# Sheet2.net
KiCad netlist of a schematic drawn in Altium Designer
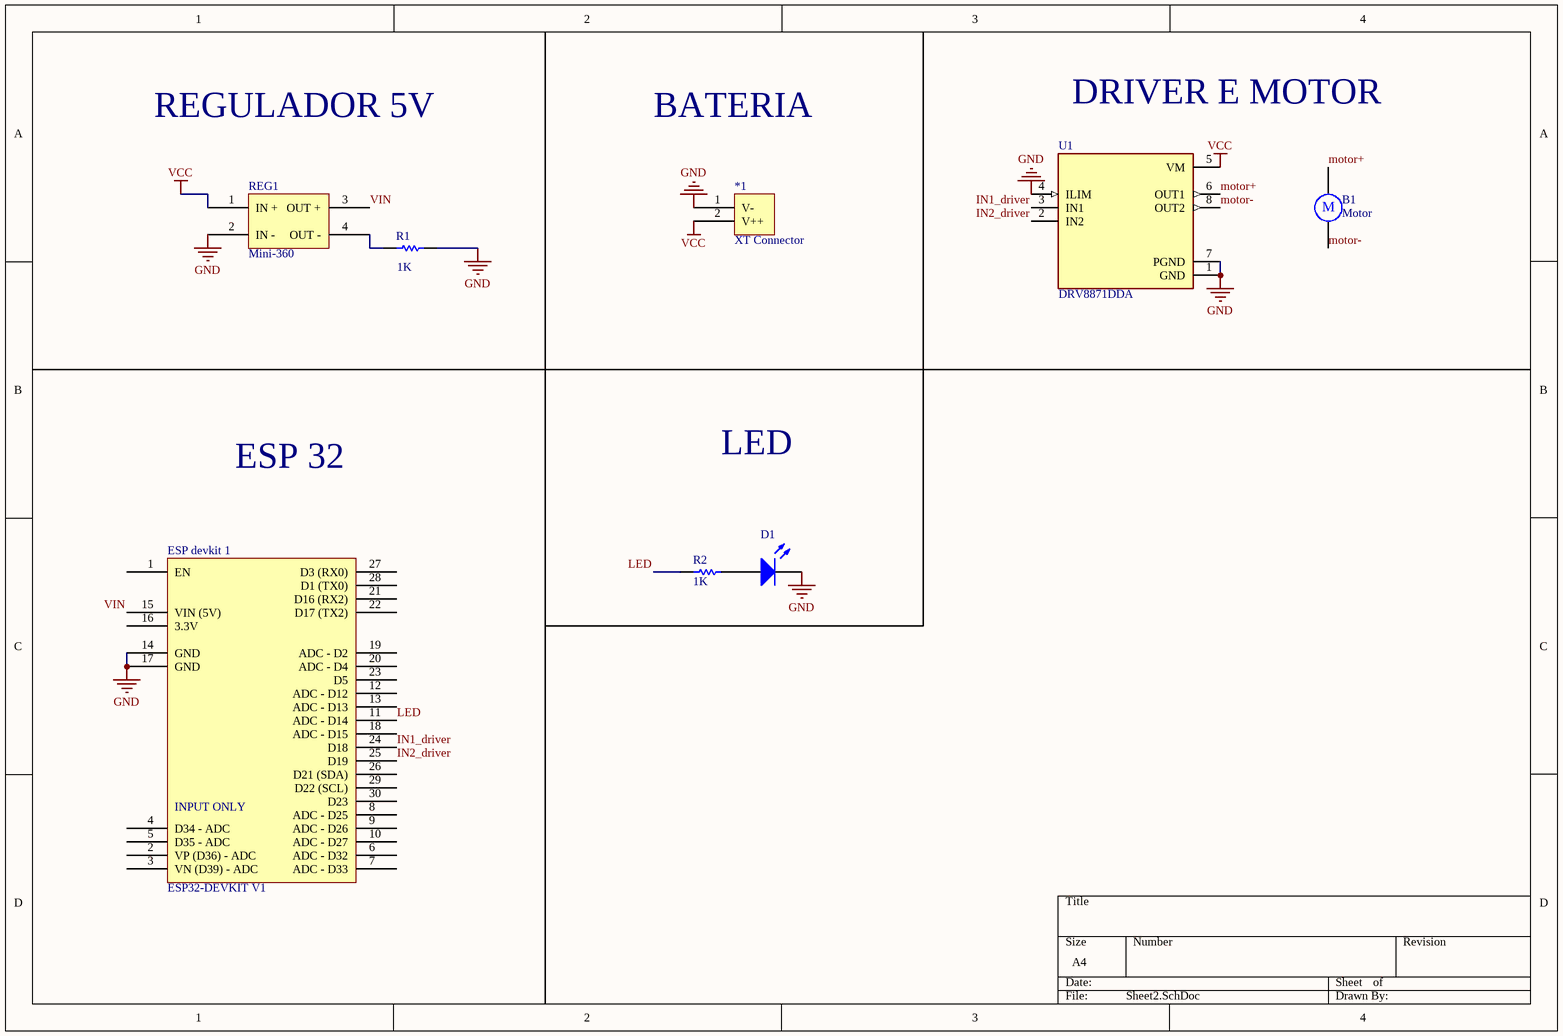
[diagram p0: Sheet2.SchDoc]

(export (version "E")
  (design (tool "Eeschema 10.0.6"))
  (components
    (comp (ref "*1")
      (value "XT Connector")
      (footprint "XT90")
      (libsource (lib "MinervaBots") (part "XT Connector"))
    )
    (comp (ref "B1")
      (value "Motor")
      (footprint "Motor")
      (description "Motor, General Kind")
      (fields (field (name "PUBLISHER") "Altium Limited"))
      (libsource (lib "MinervaBots") (part "Motor"))
    )
    (comp (ref "D1")
      (value "Light-Emitting Diode")
      (libsource (lib "Simulation Generic Components") (part "LED"))
    )
    (comp (ref "ESP devkit 1")
      (value "ESP32-DEVKIT V1")
      (footprint "ESP32-DEVKIT V1")
      (description "Placa ESP32 com 30 pinos - Modelo DEVKIT V1")
      (libsource (lib "MinervaBots") (part "ESP32-DEVKIT V1"))
    )
    (comp (ref "R1")
      (value "1K")
      (description "Resistor")
      (libsource (lib "Simulation Generic Components") (part "Resistor"))
    )
    (comp (ref "R2")
      (value "1K")
      (description "Resistor")
      (libsource (lib "Simulation Generic Components") (part "Resistor"))
    )
    (comp (ref "REG1")
      (value "Mini-360")
      (footprint "Mini-360")
      (description "Módulo Regulador de Tensão Step Down Buck DC-DC Mini 360 3A")
      (libsource (lib "MinervaBots") (part "Mini-360"))
    )
    (comp (ref "U1")
      (value "DRV8871DDA")
      (footprint "DRV8871DDAR")
      (description "45-V, 3.6-A H-bridge motor driver with integrated current sensing 8-SO PowerPAD -40 to 125")
      (fields (field (name "MF") "Texas Instruments"))
      (libsource (lib "MinervaBots") (part "DRV8871DDA"))
    )
  )
  (nets
    (net (code "1") (name "/IN1_driver") (class "Default")
      (node (ref "ESP devkit 1") (pin "24") (pinfunction "D18_24") (pintype "passive"))
      (node (ref "U1") (pin "3") (pinfunction "IN1_3") (pintype "passive"))
    )
    (net (code "2") (name "/IN2_driver") (class "Default")
      (node (ref "ESP devkit 1") (pin "25") (pinfunction "D19_25") (pintype "passive"))
      (node (ref "U1") (pin "2") (pinfunction "IN2_2") (pintype "passive"))
    )
    (net (code "3") (name "/LED") (class "Default")
      (node (ref "ESP devkit 1") (pin "11") (pinfunction "ADC_-_D14_11") (pintype "passive"))
      (node (ref "R2") (pin "1") (pinfunction "1_1") (pintype "passive"))
    )
    (net (code "4") (name "/VIN") (class "Default")
      (node (ref "ESP devkit 1") (pin "15") (pinfunction "VIN_(5V)_15") (pintype "passive"))
      (node (ref "REG1") (pin "3") (pinfunction "OUT_+_3") (pintype "power_in"))
    )
    (net (code "5") (name "/motor+") (class "Default")
      (node (ref "B1") (pin "1") (pinfunction "1_1") (pintype "passive"))
      (node (ref "U1") (pin "6") (pinfunction "OUT1_6") (pintype "output"))
    )
    (net (code "6") (name "/motor-") (class "Default")
      (node (ref "B1") (pin "2") (pinfunction "2_2") (pintype "passive"))
      (node (ref "U1") (pin "8") (pinfunction "OUT2_8") (pintype "output"))
    )
    (net (code "7") (name "GND") (class "Default")
      (node (ref "*1") (pin "1") (pinfunction "V-_1") (pintype "passive"))
      (node (ref "D1") (pin "2") (pinfunction "K_2") (pintype "passive"))
      (node (ref "ESP devkit 1") (pin "14") (pinfunction "GND_14") (pintype "passive"))
      (node (ref "ESP devkit 1") (pin "17") (pinfunction "GND_17") (pintype "passive"))
      (node (ref "R1") (pin "2") (pinfunction "2_2") (pintype "passive"))
      (node (ref "REG1") (pin "2") (pinfunction "IN_-_2") (pintype "power_in"))
      (node (ref "U1") (pin "1") (pinfunction "GND_1") (pintype "power_in"))
      (node (ref "U1") (pin "4") (pinfunction "ILIM_4") (pintype "input"))
      (node (ref "U1") (pin "7") (pinfunction "PGND_7") (pintype "power_in"))
    )
    (net (code "8") (name "Net-(D1-A)") (class "Default")
      (node (ref "D1") (pin "1") (pinfunction "A_1") (pintype "passive"))
      (node (ref "R2") (pin "2") (pinfunction "2_2") (pintype "passive"))
    )
    (net (code "9") (name "Net-(REG1-OUT_-)") (class "Default")
      (node (ref "R1") (pin "1") (pinfunction "1_1") (pintype "passive"))
      (node (ref "REG1") (pin "4") (pinfunction "OUT_-_4") (pintype "power_in"))
    )
    (net (code "10") (name "VCC") (class "Default")
      (node (ref "*1") (pin "2") (pinfunction "V++_2") (pintype "passive"))
      (node (ref "REG1") (pin "1") (pinfunction "IN_+_1") (pintype "power_in"))
      (node (ref "U1") (pin "5") (pinfunction "VM_5") (pintype "power_in"))
    )
    (net (code "11") (name "unconnected-(ESP devkit 1-3.3V-Pad16)") (class "Default")
      (node (ref "ESP devkit 1") (pin "16") (pinfunction "3.3V_16") (pintype "passive"))
    )
    (net (code "12") (name "unconnected-(ESP devkit 1-ADC_-_D2-Pad19)") (class "Default")
      (node (ref "ESP devkit 1") (pin "19") (pinfunction "ADC_-_D2_19") (pintype "passive"))
    )
    (net (code "13") (name "unconnected-(ESP devkit 1-ADC_-_D4-Pad20)") (class "Default")
      (node (ref "ESP devkit 1") (pin "20") (pinfunction "ADC_-_D4_20") (pintype "passive"))
    )
    (net (code "14") (name "unconnected-(ESP devkit 1-ADC_-_D12-Pad12)") (class "Default")
      (node (ref "ESP devkit 1") (pin "12") (pinfunction "ADC_-_D12_12") (pintype "passive"))
    )
    (net (code "15") (name "unconnected-(ESP devkit 1-ADC_-_D13-Pad13)") (class "Default")
      (node (ref "ESP devkit 1") (pin "13") (pinfunction "ADC_-_D13_13") (pintype "passive"))
    )
    (net (code "16") (name "unconnected-(ESP devkit 1-ADC_-_D15-Pad18)") (class "Default")
      (node (ref "ESP devkit 1") (pin "18") (pinfunction "ADC_-_D15_18") (pintype "passive"))
    )
    (net (code "17") (name "unconnected-(ESP devkit 1-ADC_-_D25-Pad8)") (class "Default")
      (node (ref "ESP devkit 1") (pin "8") (pinfunction "ADC_-_D25_8") (pintype "passive"))
    )
    (net (code "18") (name "unconnected-(ESP devkit 1-ADC_-_D26-Pad9)") (class "Default")
      (node (ref "ESP devkit 1") (pin "9") (pinfunction "ADC_-_D26_9") (pintype "passive"))
    )
    (net (code "19") (name "unconnected-(ESP devkit 1-ADC_-_D27-Pad10)") (class "Default")
      (node (ref "ESP devkit 1") (pin "10") (pinfunction "ADC_-_D27_10") (pintype "passive"))
    )
    (net (code "20") (name "unconnected-(ESP devkit 1-ADC_-_D32-Pad6)") (class "Default")
      (node (ref "ESP devkit 1") (pin "6") (pinfunction "ADC_-_D32_6") (pintype "passive"))
    )
    (net (code "21") (name "unconnected-(ESP devkit 1-ADC_-_D33-Pad7)") (class "Default")
      (node (ref "ESP devkit 1") (pin "7") (pinfunction "ADC_-_D33_7") (pintype "passive"))
    )
    (net (code "22") (name "unconnected-(ESP devkit 1-D1_(TX0)-Pad28)") (class "Default")
      (node (ref "ESP devkit 1") (pin "28") (pinfunction "D1_(TX0)_28") (pintype "passive"))
    )
    (net (code "23") (name "unconnected-(ESP devkit 1-D3_(RX0)-Pad27)") (class "Default")
      (node (ref "ESP devkit 1") (pin "27") (pinfunction "D3_(RX0)_27") (pintype "passive"))
    )
    (net (code "24") (name "unconnected-(ESP devkit 1-D5-Pad23)") (class "Default")
      (node (ref "ESP devkit 1") (pin "23") (pinfunction "D5_23") (pintype "passive"))
    )
    (net (code "25") (name "unconnected-(ESP devkit 1-D16_(RX2)-Pad21)") (class "Default")
      (node (ref "ESP devkit 1") (pin "21") (pinfunction "D16_(RX2)_21") (pintype "passive"))
    )
    (net (code "26") (name "unconnected-(ESP devkit 1-D17_(TX2)-Pad22)") (class "Default")
      (node (ref "ESP devkit 1") (pin "22") (pinfunction "D17_(TX2)_22") (pintype "passive"))
    )
    (net (code "27") (name "unconnected-(ESP devkit 1-D21_(SDA)-Pad26)") (class "Default")
      (node (ref "ESP devkit 1") (pin "26") (pinfunction "D21_(SDA)_26") (pintype "passive"))
    )
    (net (code "28") (name "unconnected-(ESP devkit 1-D22_(SCL)-Pad29)") (class "Default")
      (node (ref "ESP devkit 1") (pin "29") (pinfunction "D22_(SCL)_29") (pintype "passive"))
    )
    (net (code "29") (name "unconnected-(ESP devkit 1-D23-Pad30)") (class "Default")
      (node (ref "ESP devkit 1") (pin "30") (pinfunction "D23_30") (pintype "passive"))
    )
    (net (code "30") (name "unconnected-(ESP devkit 1-D34_-_ADC-Pad4)") (class "Default")
      (node (ref "ESP devkit 1") (pin "4") (pinfunction "D34_-_ADC_4") (pintype "passive"))
    )
    (net (code "31") (name "unconnected-(ESP devkit 1-D35_-_ADC-Pad5)") (class "Default")
      (node (ref "ESP devkit 1") (pin "5") (pinfunction "D35_-_ADC_5") (pintype "passive"))
    )
    (net (code "32") (name "unconnected-(ESP devkit 1-EN-Pad1)") (class "Default")
      (node (ref "ESP devkit 1") (pin "1") (pinfunction "EN_1") (pintype "passive"))
    )
    (net (code "33") (name "unconnected-(ESP devkit 1-VN_(D39)_-_ADC-Pad3)") (class "Default")
      (node (ref "ESP devkit 1") (pin "3") (pinfunction "VN_(D39)_-_ADC_3") (pintype "passive"))
    )
    (net (code "34") (name "unconnected-(ESP devkit 1-VP_(D36)_-_ADC-Pad2)") (class "Default")
      (node (ref "ESP devkit 1") (pin "2") (pinfunction "VP_(D36)_-_ADC_2") (pintype "passive"))
    )
  )
)
